# 11-1121-2_ABC_GPIO_RELAY.net
KiCad netlist of a schematic drawn in EAGLE
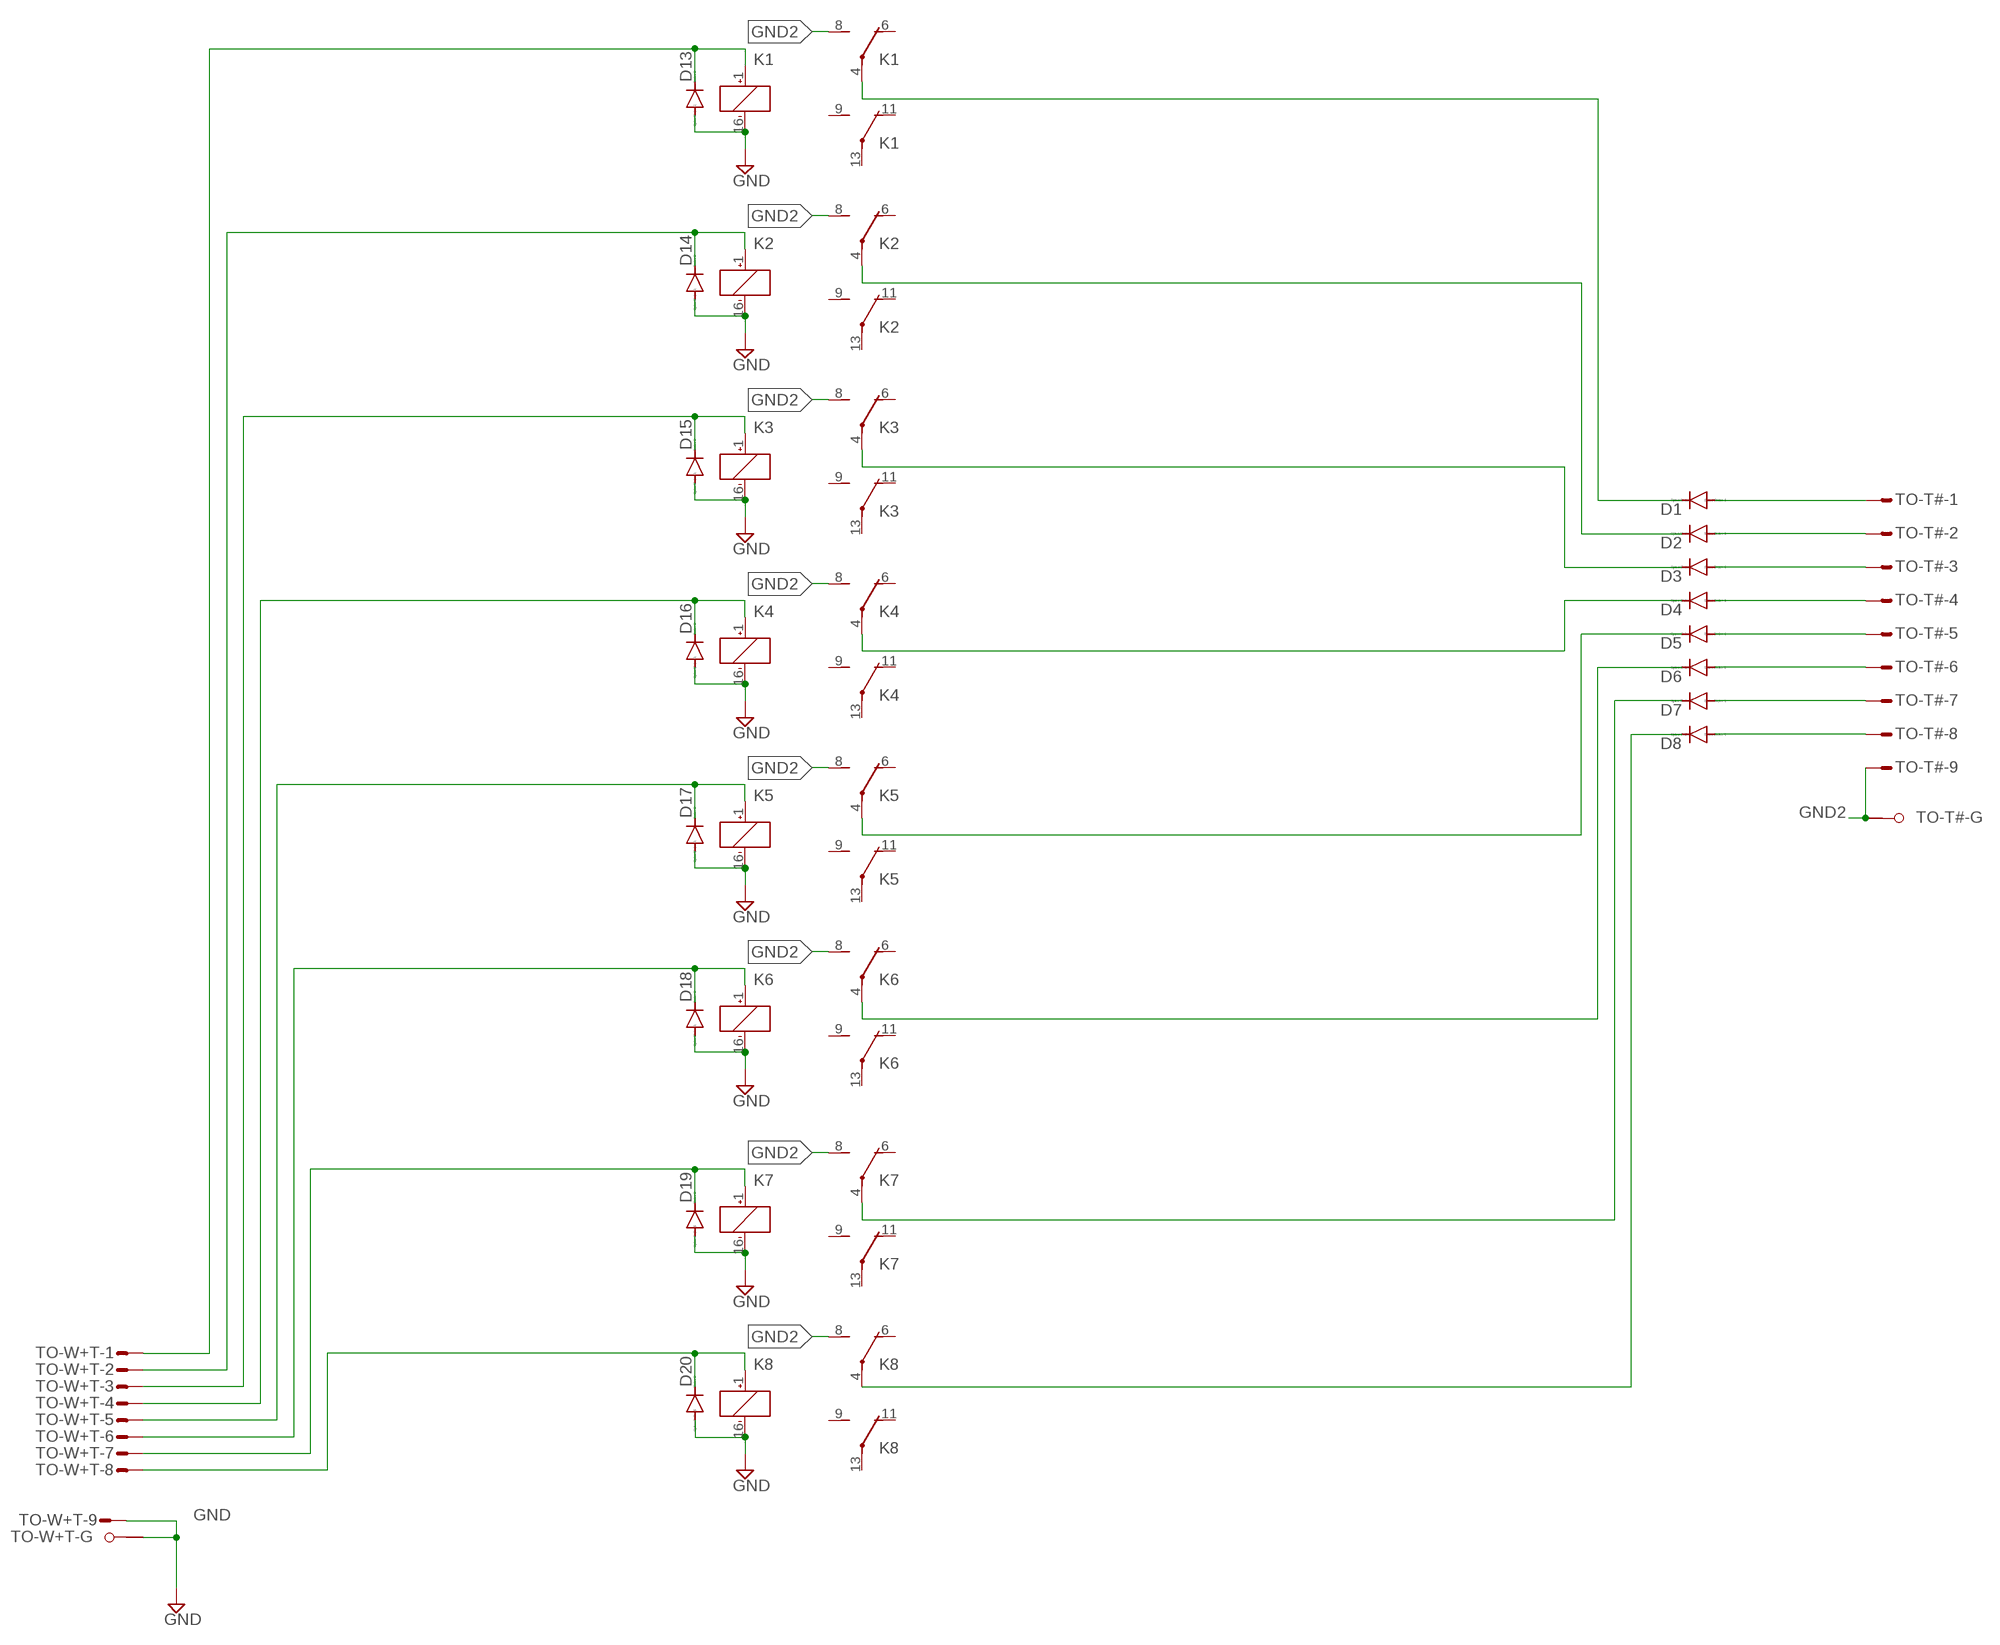
[diagram p0: schematic, sheet 1]

(export (version "E")
  (design (tool "Eeschema 10.0.6"))
  (components
    (comp (ref "D1")
      (value "DIODE-DO214AA")
      (footprint "eagle-import:DO214AA")
      (libsource (lib "eagle-import") (part "DIODE-DO214AA"))
    )
    (comp (ref "D2")
      (value "DIODE-DO214AA")
      (footprint "eagle-import:DO214AA")
      (libsource (lib "eagle-import") (part "DIODE-DO214AA"))
    )
    (comp (ref "D3")
      (value "DIODE-DO214AA")
      (footprint "eagle-import:DO214AA")
      (libsource (lib "eagle-import") (part "DIODE-DO214AA"))
    )
    (comp (ref "D4")
      (value "DIODE-DO214AA")
      (footprint "eagle-import:DO214AA")
      (libsource (lib "eagle-import") (part "DIODE-DO214AA"))
    )
    (comp (ref "D5")
      (value "DIODE-DO214AA")
      (footprint "eagle-import:DO214AA")
      (libsource (lib "eagle-import") (part "DIODE-DO214AA"))
    )
    (comp (ref "D6")
      (value "DIODE-DO214AA")
      (footprint "eagle-import:DO214AA")
      (libsource (lib "eagle-import") (part "DIODE-DO214AA"))
    )
    (comp (ref "D7")
      (value "DIODE-DO214AA")
      (footprint "eagle-import:DO214AA")
      (libsource (lib "eagle-import") (part "DIODE-DO214AA"))
    )
    (comp (ref "D8")
      (value "DIODE-DO214AA")
      (footprint "eagle-import:DO214AA")
      (libsource (lib "eagle-import") (part "DIODE-DO214AA"))
    )
    (comp (ref "D13")
      (value "DIODE-DO214AA")
      (footprint "eagle-import:DO214AA")
      (libsource (lib "eagle-import") (part "DIODE-DO214AA"))
    )
    (comp (ref "D14")
      (value "DIODE-DO214AA")
      (footprint "eagle-import:DO214AA")
      (libsource (lib "eagle-import") (part "DIODE-DO214AA"))
    )
    (comp (ref "D15")
      (value "DIODE-DO214AA")
      (footprint "eagle-import:DO214AA")
      (libsource (lib "eagle-import") (part "DIODE-DO214AA"))
    )
    (comp (ref "D16")
      (value "DIODE-DO214AA")
      (footprint "eagle-import:DO214AA")
      (libsource (lib "eagle-import") (part "DIODE-DO214AA"))
    )
    (comp (ref "D17")
      (value "DIODE-DO214AA")
      (footprint "eagle-import:DO214AA")
      (libsource (lib "eagle-import") (part "DIODE-DO214AA"))
    )
    (comp (ref "D18")
      (value "DIODE-DO214AA")
      (footprint "eagle-import:DO214AA")
      (libsource (lib "eagle-import") (part "DIODE-DO214AA"))
    )
    (comp (ref "D19")
      (value "DIODE-DO214AA")
      (footprint "eagle-import:DO214AA")
      (libsource (lib "eagle-import") (part "DIODE-DO214AA"))
    )
    (comp (ref "D20")
      (value "DIODE-DO214AA")
      (footprint "eagle-import:DO214AA")
      (libsource (lib "eagle-import") (part "DIODE-DO214AA"))
    )
    (comp (ref "K1")
      (value "DS2Y-S-DC12V")
      (footprint "eagle-import:DS2Y")
      (libsource (lib "eagle-import") (part "DS2Y-S-DC12V"))
    )
    (comp (ref "K2")
      (value "DS2Y-S-DC12V")
      (footprint "eagle-import:DS2Y")
      (libsource (lib "eagle-import") (part "DS2Y-S-DC12V"))
    )
    (comp (ref "K3")
      (value "DS2Y-S-DC12V")
      (footprint "eagle-import:DS2Y")
      (libsource (lib "eagle-import") (part "DS2Y-S-DC12V"))
    )
    (comp (ref "K4")
      (value "DS2Y-S-DC12V")
      (footprint "eagle-import:DS2Y")
      (libsource (lib "eagle-import") (part "DS2Y-S-DC12V"))
    )
    (comp (ref "K5")
      (value "DS2Y-S-DC12V")
      (footprint "eagle-import:DS2Y")
      (libsource (lib "eagle-import") (part "DS2Y-S-DC12V"))
    )
    (comp (ref "K6")
      (value "DS2Y-S-DC12V")
      (footprint "eagle-import:DS2Y")
      (libsource (lib "eagle-import") (part "DS2Y-S-DC12V"))
    )
    (comp (ref "K7")
      (value "DS2Y-S-DC12V")
      (footprint "eagle-import:DS2Y")
      (libsource (lib "eagle-import") (part "DS2Y-S-DC12V"))
    )
    (comp (ref "K8")
      (value "DS2Y-S-DC12V")
      (footprint "eagle-import:DS2Y")
      (libsource (lib "eagle-import") (part "DS2Y-S-DC12V"))
    )
    (comp (ref "TO-T#")
      (value "M09HPS")
      (footprint "eagle-import:M09HP")
      (libsource (lib "eagle-import") (part "M09HPS"))
    )
    (comp (ref "TO-W+T")
      (value "M09HPS")
      (footprint "eagle-import:M09HP")
      (libsource (lib "eagle-import") (part "M09HPS"))
    )
  )
  (nets
    (net (code "1") (name "GND") (class "Default")
      (node (ref "D13") (pin "A") (pinfunction "A_A") (pintype "passive"))
      (node (ref "D14") (pin "A") (pinfunction "A_A") (pintype "passive"))
      (node (ref "D15") (pin "A") (pinfunction "A_A") (pintype "passive"))
      (node (ref "D16") (pin "A") (pinfunction "A_A") (pintype "passive"))
      (node (ref "D17") (pin "A") (pinfunction "A_A") (pintype "passive"))
      (node (ref "D18") (pin "A") (pinfunction "A_A") (pintype "passive"))
      (node (ref "D19") (pin "A") (pinfunction "A_A") (pintype "passive"))
      (node (ref "D20") (pin "A") (pinfunction "A_A") (pintype "passive"))
      (node (ref "K1") (pin "16") (pinfunction "-_16") (pintype "passive"))
      (node (ref "K2") (pin "16") (pinfunction "-_16") (pintype "passive"))
      (node (ref "K3") (pin "16") (pinfunction "-_16") (pintype "passive"))
      (node (ref "K4") (pin "16") (pinfunction "-_16") (pintype "passive"))
      (node (ref "K5") (pin "16") (pinfunction "-_16") (pintype "passive"))
      (node (ref "K6") (pin "16") (pinfunction "-_16") (pintype "passive"))
      (node (ref "K7") (pin "16") (pinfunction "-_16") (pintype "passive"))
      (node (ref "K8") (pin "16") (pinfunction "-_16") (pintype "passive"))
      (node (ref "TO-W+T") (pin "9") (pinfunction "M_9") (pintype "passive"))
      (node (ref "TO-W+T") (pin "G1") (pinfunction "G1_G1") (pintype "passive"))
    )
    (net (code "2") (name "GND2") (class "Default")
      (node (ref "K1") (pin "8") (pinfunction "S_8") (pintype "passive"))
      (node (ref "K2") (pin "8") (pinfunction "S_8") (pintype "passive"))
      (node (ref "K3") (pin "8") (pinfunction "S_8") (pintype "passive"))
      (node (ref "K4") (pin "8") (pinfunction "S_8") (pintype "passive"))
      (node (ref "K5") (pin "8") (pinfunction "S_8") (pintype "passive"))
      (node (ref "K6") (pin "8") (pinfunction "S_8") (pintype "passive"))
      (node (ref "K7") (pin "8") (pinfunction "S_8") (pintype "passive"))
      (node (ref "K8") (pin "8") (pinfunction "S_8") (pintype "passive"))
      (node (ref "TO-T#") (pin "9") (pinfunction "M_9") (pintype "passive"))
      (node (ref "TO-T#") (pin "G1") (pinfunction "G1_G1") (pintype "passive"))
    )
    (net (code "3") (name "Net-(K1A-+)") (class "Default")
      (node (ref "D13") (pin "C") (pinfunction "C_C") (pintype "passive"))
      (node (ref "K1") (pin "1") (pinfunction "+_1") (pintype "passive"))
      (node (ref "TO-W+T") (pin "1") (pinfunction "M_1") (pintype "passive"))
    )
    (net (code "4") (name "Net-(K1B-P)") (class "Default")
      (node (ref "D1") (pin "C") (pinfunction "C_C") (pintype "passive"))
      (node (ref "K1") (pin "4") (pinfunction "P_4") (pintype "passive"))
    )
    (net (code "5") (name "Net-(K2A-+)") (class "Default")
      (node (ref "D14") (pin "C") (pinfunction "C_C") (pintype "passive"))
      (node (ref "K2") (pin "1") (pinfunction "+_1") (pintype "passive"))
      (node (ref "TO-W+T") (pin "2") (pinfunction "M_2") (pintype "passive"))
    )
    (net (code "6") (name "Net-(K2B-P)") (class "Default")
      (node (ref "D2") (pin "C") (pinfunction "C_C") (pintype "passive"))
      (node (ref "K2") (pin "4") (pinfunction "P_4") (pintype "passive"))
    )
    (net (code "7") (name "Net-(K3A-+)") (class "Default")
      (node (ref "D15") (pin "C") (pinfunction "C_C") (pintype "passive"))
      (node (ref "K3") (pin "1") (pinfunction "+_1") (pintype "passive"))
      (node (ref "TO-W+T") (pin "3") (pinfunction "M_3") (pintype "passive"))
    )
    (net (code "8") (name "Net-(K3B-P)") (class "Default")
      (node (ref "D3") (pin "C") (pinfunction "C_C") (pintype "passive"))
      (node (ref "K3") (pin "4") (pinfunction "P_4") (pintype "passive"))
    )
    (net (code "9") (name "Net-(K4A-+)") (class "Default")
      (node (ref "D16") (pin "C") (pinfunction "C_C") (pintype "passive"))
      (node (ref "K4") (pin "1") (pinfunction "+_1") (pintype "passive"))
      (node (ref "TO-W+T") (pin "4") (pinfunction "M_4") (pintype "passive"))
    )
    (net (code "10") (name "Net-(K4B-P)") (class "Default")
      (node (ref "D4") (pin "C") (pinfunction "C_C") (pintype "passive"))
      (node (ref "K4") (pin "4") (pinfunction "P_4") (pintype "passive"))
    )
    (net (code "11") (name "Net-(K5A-+)") (class "Default")
      (node (ref "D17") (pin "C") (pinfunction "C_C") (pintype "passive"))
      (node (ref "K5") (pin "1") (pinfunction "+_1") (pintype "passive"))
      (node (ref "TO-W+T") (pin "5") (pinfunction "M_5") (pintype "passive"))
    )
    (net (code "12") (name "Net-(K5B-P)") (class "Default")
      (node (ref "D5") (pin "C") (pinfunction "C_C") (pintype "passive"))
      (node (ref "K5") (pin "4") (pinfunction "P_4") (pintype "passive"))
    )
    (net (code "13") (name "Net-(K6A-+)") (class "Default")
      (node (ref "D18") (pin "C") (pinfunction "C_C") (pintype "passive"))
      (node (ref "K6") (pin "1") (pinfunction "+_1") (pintype "passive"))
      (node (ref "TO-W+T") (pin "6") (pinfunction "M_6") (pintype "passive"))
    )
    (net (code "14") (name "Net-(K6B-P)") (class "Default")
      (node (ref "D6") (pin "C") (pinfunction "C_C") (pintype "passive"))
      (node (ref "K6") (pin "4") (pinfunction "P_4") (pintype "passive"))
    )
    (net (code "15") (name "Net-(K7A-+)") (class "Default")
      (node (ref "D19") (pin "C") (pinfunction "C_C") (pintype "passive"))
      (node (ref "K7") (pin "1") (pinfunction "+_1") (pintype "passive"))
      (node (ref "TO-W+T") (pin "7") (pinfunction "M_7") (pintype "passive"))
    )
    (net (code "16") (name "Net-(K7B-P)") (class "Default")
      (node (ref "D7") (pin "C") (pinfunction "C_C") (pintype "passive"))
      (node (ref "K7") (pin "4") (pinfunction "P_4") (pintype "passive"))
    )
    (net (code "17") (name "Net-(K8A-+)") (class "Default")
      (node (ref "D20") (pin "C") (pinfunction "C_C") (pintype "passive"))
      (node (ref "K8") (pin "1") (pinfunction "+_1") (pintype "passive"))
      (node (ref "TO-W+T") (pin "8") (pinfunction "M_8") (pintype "passive"))
    )
    (net (code "18") (name "Net-(K8B-P)") (class "Default")
      (node (ref "D8") (pin "C") (pinfunction "C_C") (pintype "passive"))
      (node (ref "K8") (pin "4") (pinfunction "P_4") (pintype "passive"))
    )
    (net (code "19") (name "Net-(TO-T#A-M)") (class "Default")
      (node (ref "D1") (pin "A") (pinfunction "A_A") (pintype "passive"))
      (node (ref "TO-T#") (pin "1") (pinfunction "M_1") (pintype "passive"))
    )
    (net (code "20") (name "Net-(TO-T#B-M)") (class "Default")
      (node (ref "D2") (pin "A") (pinfunction "A_A") (pintype "passive"))
      (node (ref "TO-T#") (pin "2") (pinfunction "M_2") (pintype "passive"))
    )
    (net (code "21") (name "Net-(TO-T#C-M)") (class "Default")
      (node (ref "D3") (pin "A") (pinfunction "A_A") (pintype "passive"))
      (node (ref "TO-T#") (pin "3") (pinfunction "M_3") (pintype "passive"))
    )
    (net (code "22") (name "Net-(TO-T#D-M)") (class "Default")
      (node (ref "D4") (pin "A") (pinfunction "A_A") (pintype "passive"))
      (node (ref "TO-T#") (pin "4") (pinfunction "M_4") (pintype "passive"))
    )
    (net (code "23") (name "Net-(TO-T#E-M)") (class "Default")
      (node (ref "D5") (pin "A") (pinfunction "A_A") (pintype "passive"))
      (node (ref "TO-T#") (pin "5") (pinfunction "M_5") (pintype "passive"))
    )
    (net (code "24") (name "Net-(TO-T#F-M)") (class "Default")
      (node (ref "D6") (pin "A") (pinfunction "A_A") (pintype "passive"))
      (node (ref "TO-T#") (pin "6") (pinfunction "M_6") (pintype "passive"))
    )
    (net (code "25") (name "Net-(TO-T#G-M)") (class "Default")
      (node (ref "D7") (pin "A") (pinfunction "A_A") (pintype "passive"))
      (node (ref "TO-T#") (pin "7") (pinfunction "M_7") (pintype "passive"))
    )
    (net (code "26") (name "Net-(TO-T#H-M)") (class "Default")
      (node (ref "D8") (pin "A") (pinfunction "A_A") (pintype "passive"))
      (node (ref "TO-T#") (pin "8") (pinfunction "M_8") (pintype "passive"))
    )
    (net (code "27") (name "unconnected-(K1B-O-Pad6)") (class "Default")
      (node (ref "K1") (pin "6") (pinfunction "O_6") (pintype "passive"))
    )
    (net (code "28") (name "unconnected-(K1C-O-Pad11)") (class "Default")
      (node (ref "K1") (pin "11") (pinfunction "O_11") (pintype "passive"))
    )
    (net (code "29") (name "unconnected-(K1C-P-Pad13)") (class "Default")
      (node (ref "K1") (pin "13") (pinfunction "P_13") (pintype "passive"))
    )
    (net (code "30") (name "unconnected-(K1C-S-Pad9)") (class "Default")
      (node (ref "K1") (pin "9") (pinfunction "S_9") (pintype "passive"))
    )
    (net (code "31") (name "unconnected-(K2B-O-Pad6)") (class "Default")
      (node (ref "K2") (pin "6") (pinfunction "O_6") (pintype "passive"))
    )
    (net (code "32") (name "unconnected-(K2C-O-Pad11)") (class "Default")
      (node (ref "K2") (pin "11") (pinfunction "O_11") (pintype "passive"))
    )
    (net (code "33") (name "unconnected-(K2C-P-Pad13)") (class "Default")
      (node (ref "K2") (pin "13") (pinfunction "P_13") (pintype "passive"))
    )
    (net (code "34") (name "unconnected-(K2C-S-Pad9)") (class "Default")
      (node (ref "K2") (pin "9") (pinfunction "S_9") (pintype "passive"))
    )
    (net (code "35") (name "unconnected-(K3B-O-Pad6)") (class "Default")
      (node (ref "K3") (pin "6") (pinfunction "O_6") (pintype "passive"))
    )
    (net (code "36") (name "unconnected-(K3C-O-Pad11)") (class "Default")
      (node (ref "K3") (pin "11") (pinfunction "O_11") (pintype "passive"))
    )
    (net (code "37") (name "unconnected-(K3C-P-Pad13)") (class "Default")
      (node (ref "K3") (pin "13") (pinfunction "P_13") (pintype "passive"))
    )
    (net (code "38") (name "unconnected-(K3C-S-Pad9)") (class "Default")
      (node (ref "K3") (pin "9") (pinfunction "S_9") (pintype "passive"))
    )
    (net (code "39") (name "unconnected-(K4B-O-Pad6)") (class "Default")
      (node (ref "K4") (pin "6") (pinfunction "O_6") (pintype "passive"))
    )
    (net (code "40") (name "unconnected-(K4C-O-Pad11)") (class "Default")
      (node (ref "K4") (pin "11") (pinfunction "O_11") (pintype "passive"))
    )
    (net (code "41") (name "unconnected-(K4C-P-Pad13)") (class "Default")
      (node (ref "K4") (pin "13") (pinfunction "P_13") (pintype "passive"))
    )
    (net (code "42") (name "unconnected-(K4C-S-Pad9)") (class "Default")
      (node (ref "K4") (pin "9") (pinfunction "S_9") (pintype "passive"))
    )
    (net (code "43") (name "unconnected-(K5B-O-Pad6)") (class "Default")
      (node (ref "K5") (pin "6") (pinfunction "O_6") (pintype "passive"))
    )
    (net (code "44") (name "unconnected-(K5C-O-Pad11)") (class "Default")
      (node (ref "K5") (pin "11") (pinfunction "O_11") (pintype "passive"))
    )
    (net (code "45") (name "unconnected-(K5C-P-Pad13)") (class "Default")
      (node (ref "K5") (pin "13") (pinfunction "P_13") (pintype "passive"))
    )
    (net (code "46") (name "unconnected-(K5C-S-Pad9)") (class "Default")
      (node (ref "K5") (pin "9") (pinfunction "S_9") (pintype "passive"))
    )
    (net (code "47") (name "unconnected-(K6B-O-Pad6)") (class "Default")
      (node (ref "K6") (pin "6") (pinfunction "O_6") (pintype "passive"))
    )
    (net (code "48") (name "unconnected-(K6C-O-Pad11)") (class "Default")
      (node (ref "K6") (pin "11") (pinfunction "O_11") (pintype "passive"))
    )
    (net (code "49") (name "unconnected-(K6C-P-Pad13)") (class "Default")
      (node (ref "K6") (pin "13") (pinfunction "P_13") (pintype "passive"))
    )
    (net (code "50") (name "unconnected-(K6C-S-Pad9)") (class "Default")
      (node (ref "K6") (pin "9") (pinfunction "S_9") (pintype "passive"))
    )
    (net (code "51") (name "unconnected-(K7B-O-Pad6)") (class "Default")
      (node (ref "K7") (pin "6") (pinfunction "O_6") (pintype "passive"))
    )
    (net (code "52") (name "unconnected-(K7C-O-Pad11)") (class "Default")
      (node (ref "K7") (pin "11") (pinfunction "O_11") (pintype "passive"))
    )
    (net (code "53") (name "unconnected-(K7C-P-Pad13)") (class "Default")
      (node (ref "K7") (pin "13") (pinfunction "P_13") (pintype "passive"))
    )
    (net (code "54") (name "unconnected-(K7C-S-Pad9)") (class "Default")
      (node (ref "K7") (pin "9") (pinfunction "S_9") (pintype "passive"))
    )
    (net (code "55") (name "unconnected-(K8B-O-Pad6)") (class "Default")
      (node (ref "K8") (pin "6") (pinfunction "O_6") (pintype "passive"))
    )
    (net (code "56") (name "unconnected-(K8C-O-Pad11)") (class "Default")
      (node (ref "K8") (pin "11") (pinfunction "O_11") (pintype "passive"))
    )
    (net (code "57") (name "unconnected-(K8C-P-Pad13)") (class "Default")
      (node (ref "K8") (pin "13") (pinfunction "P_13") (pintype "passive"))
    )
    (net (code "58") (name "unconnected-(K8C-S-Pad9)") (class "Default")
      (node (ref "K8") (pin "9") (pinfunction "S_9") (pintype "passive"))
    )
    (net (code "59") (name "unconnected-(TO-T#-PadG2)") (class "Default")
      (node (ref "TO-T#") (pin "G2") (pinfunction "G2_G2") (pintype "passive"))
    )
    (net (code "60") (name "unconnected-(TO-W+T-PadG2)") (class "Default")
      (node (ref "TO-W+T") (pin "G2") (pinfunction "G2_G2") (pintype "passive"))
    )
  )
)
